# Main.net
KiCad netlist of a schematic drawn in Altium Designer
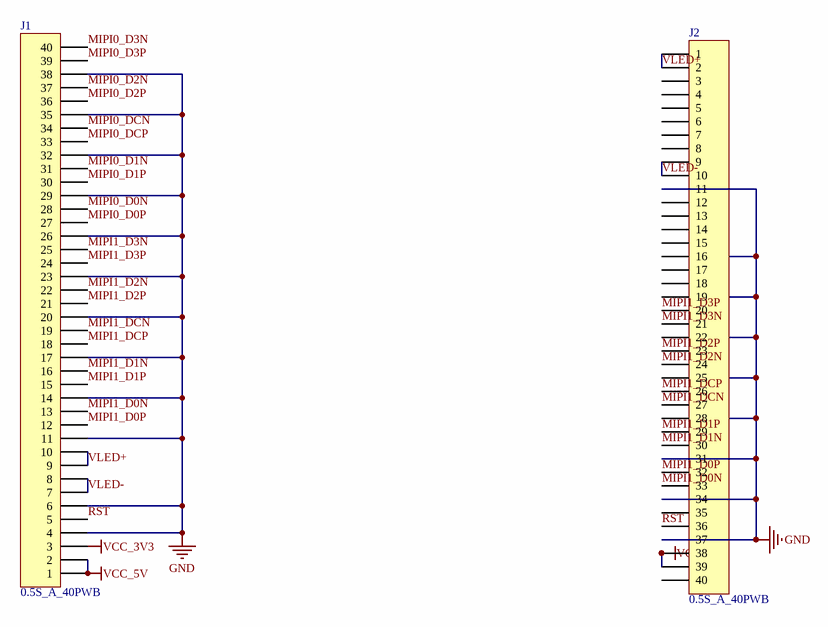
[diagram p0: Main.SchDoc]

(export (version "E")
  (design (tool "Eeschema 10.0.6"))
  (components
    (comp (ref "J1")
      (value "0.5S_A_40PWB")
      (footprint "FFC_0.5_40")
      (description "Header, 40-Pin")
      (fields (field (name "PUBLISHER") "Altium Limited"))
      (libsource (lib "MyPcbLib") (part "FPC40-0.5mm"))
    )
    (comp (ref "J2")
      (value "0.5S_A_40PWB")
      (footprint "FFC_0.5_40")
      (description "Header, 40-Pin")
      (fields (field (name "PUBLISHER") "Altium Limited"))
      (libsource (lib "") (part "FPC40-0.5mm_1"))
    )
  )
  (nets
    (net (code "1") (name "/MIPI0_D0N") (class "Default")
      (node (ref "J1") (pin "28") (pinfunction "28_28") (pintype "passive"))
    )
    (net (code "2") (name "/MIPI0_D0P") (class "Default")
      (node (ref "J1") (pin "27") (pinfunction "27_27") (pintype "passive"))
    )
    (net (code "3") (name "/MIPI0_D1N") (class "Default")
      (node (ref "J1") (pin "31") (pinfunction "31_31") (pintype "passive"))
    )
    (net (code "4") (name "/MIPI0_D1P") (class "Default")
      (node (ref "J1") (pin "30") (pinfunction "30_30") (pintype "passive"))
    )
    (net (code "5") (name "/MIPI0_D2N") (class "Default")
      (node (ref "J1") (pin "37") (pinfunction "37_37") (pintype "passive"))
    )
    (net (code "6") (name "/MIPI0_D2P") (class "Default")
      (node (ref "J1") (pin "36") (pinfunction "36_36") (pintype "passive"))
    )
    (net (code "7") (name "/MIPI0_D3N") (class "Default")
      (node (ref "J1") (pin "40") (pinfunction "40_40") (pintype "passive"))
    )
    (net (code "8") (name "/MIPI0_D3P") (class "Default")
      (node (ref "J1") (pin "39") (pinfunction "39_39") (pintype "passive"))
    )
    (net (code "9") (name "/MIPI0_DCN") (class "Default")
      (node (ref "J1") (pin "34") (pinfunction "34_34") (pintype "passive"))
    )
    (net (code "10") (name "/MIPI0_DCP") (class "Default")
      (node (ref "J1") (pin "33") (pinfunction "33_33") (pintype "passive"))
    )
    (net (code "11") (name "/MIPI1_D0N") (class "Default")
      (node (ref "J1") (pin "13") (pinfunction "13_13") (pintype "passive"))
      (node (ref "J2") (pin "33") (pinfunction "33_33") (pintype "passive"))
    )
    (net (code "12") (name "/MIPI1_D0P") (class "Default")
      (node (ref "J1") (pin "12") (pinfunction "12_12") (pintype "passive"))
      (node (ref "J2") (pin "32") (pinfunction "32_32") (pintype "passive"))
    )
    (net (code "13") (name "/MIPI1_D1N") (class "Default")
      (node (ref "J1") (pin "16") (pinfunction "16_16") (pintype "passive"))
      (node (ref "J2") (pin "30") (pinfunction "30_30") (pintype "passive"))
    )
    (net (code "14") (name "/MIPI1_D1P") (class "Default")
      (node (ref "J1") (pin "15") (pinfunction "15_15") (pintype "passive"))
      (node (ref "J2") (pin "29") (pinfunction "29_29") (pintype "passive"))
    )
    (net (code "15") (name "/MIPI1_D2N") (class "Default")
      (node (ref "J1") (pin "22") (pinfunction "22_22") (pintype "passive"))
      (node (ref "J2") (pin "24") (pinfunction "24_24") (pintype "passive"))
    )
    (net (code "16") (name "/MIPI1_D2P") (class "Default")
      (node (ref "J1") (pin "21") (pinfunction "21_21") (pintype "passive"))
      (node (ref "J2") (pin "23") (pinfunction "23_23") (pintype "passive"))
    )
    (net (code "17") (name "/MIPI1_D3N") (class "Default")
      (node (ref "J1") (pin "25") (pinfunction "25_25") (pintype "passive"))
      (node (ref "J2") (pin "21") (pinfunction "21_21") (pintype "passive"))
    )
    (net (code "18") (name "/MIPI1_D3P") (class "Default")
      (node (ref "J1") (pin "24") (pinfunction "24_24") (pintype "passive"))
      (node (ref "J2") (pin "20") (pinfunction "20_20") (pintype "passive"))
    )
    (net (code "19") (name "/MIPI1_DCN") (class "Default")
      (node (ref "J1") (pin "19") (pinfunction "19_19") (pintype "passive"))
      (node (ref "J2") (pin "27") (pinfunction "27_27") (pintype "passive"))
    )
    (net (code "20") (name "/MIPI1_DCP") (class "Default")
      (node (ref "J1") (pin "18") (pinfunction "18_18") (pintype "passive"))
      (node (ref "J2") (pin "26") (pinfunction "26_26") (pintype "passive"))
    )
    (net (code "21") (name "/RST") (class "Default")
      (node (ref "J1") (pin "5") (pinfunction "5_5") (pintype "passive"))
      (node (ref "J2") (pin "36") (pinfunction "36_36") (pintype "passive"))
    )
    (net (code "22") (name "/VLED+") (class "Default")
      (node (ref "J1") (pin "10") (pinfunction "10_10") (pintype "passive"))
      (node (ref "J1") (pin "9") (pinfunction "9_9") (pintype "passive"))
      (node (ref "J2") (pin "1") (pinfunction "1_1") (pintype "passive"))
      (node (ref "J2") (pin "2") (pinfunction "2_2") (pintype "passive"))
    )
    (net (code "23") (name "/VLED-") (class "Default")
      (node (ref "J1") (pin "7") (pinfunction "7_7") (pintype "passive"))
      (node (ref "J1") (pin "8") (pinfunction "8_8") (pintype "passive"))
      (node (ref "J2") (pin "10") (pinfunction "10_10") (pintype "passive"))
      (node (ref "J2") (pin "9") (pinfunction "9_9") (pintype "passive"))
    )
    (net (code "24") (name "GND") (class "Default")
      (node (ref "J1") (pin "11") (pinfunction "11_11") (pintype "passive"))
      (node (ref "J1") (pin "14") (pinfunction "14_14") (pintype "passive"))
      (node (ref "J1") (pin "17") (pinfunction "17_17") (pintype "passive"))
      (node (ref "J1") (pin "20") (pinfunction "20_20") (pintype "passive"))
      (node (ref "J1") (pin "23") (pinfunction "23_23") (pintype "passive"))
      (node (ref "J1") (pin "26") (pinfunction "26_26") (pintype "passive"))
      (node (ref "J1") (pin "29") (pinfunction "29_29") (pintype "passive"))
      (node (ref "J1") (pin "32") (pinfunction "32_32") (pintype "passive"))
      (node (ref "J1") (pin "35") (pinfunction "35_35") (pintype "passive"))
      (node (ref "J1") (pin "38") (pinfunction "38_38") (pintype "passive"))
      (node (ref "J1") (pin "4") (pinfunction "4_4") (pintype "passive"))
      (node (ref "J1") (pin "6") (pinfunction "6_6") (pintype "passive"))
      (node (ref "J2") (pin "11") (pinfunction "11_11") (pintype "passive"))
      (node (ref "J2") (pin "16") (pinfunction "16_16") (pintype "passive"))
      (node (ref "J2") (pin "19") (pinfunction "19_19") (pintype "passive"))
      (node (ref "J2") (pin "22") (pinfunction "22_22") (pintype "passive"))
      (node (ref "J2") (pin "25") (pinfunction "25_25") (pintype "passive"))
      (node (ref "J2") (pin "28") (pinfunction "28_28") (pintype "passive"))
      (node (ref "J2") (pin "31") (pinfunction "31_31") (pintype "passive"))
      (node (ref "J2") (pin "34") (pinfunction "34_34") (pintype "passive"))
      (node (ref "J2") (pin "37") (pinfunction "37_37") (pintype "passive"))
    )
    (net (code "25") (name "VCC_3V3") (class "Default")
      (node (ref "J1") (pin "3") (pinfunction "3_3") (pintype "passive"))
      (node (ref "J2") (pin "38") (pinfunction "38_38") (pintype "passive"))
      (node (ref "J2") (pin "39") (pinfunction "39_39") (pintype "passive"))
    )
    (net (code "26") (name "VCC_5V") (class "Default")
      (node (ref "J1") (pin "1") (pinfunction "1_1") (pintype "passive"))
      (node (ref "J1") (pin "2") (pinfunction "2_2") (pintype "passive"))
    )
    (net (code "27") (name "unconnected-(J2-Pad3)") (class "Default")
      (node (ref "J2") (pin "3") (pinfunction "3_3") (pintype "passive"))
    )
    (net (code "28") (name "unconnected-(J2-Pad4)") (class "Default")
      (node (ref "J2") (pin "4") (pinfunction "4_4") (pintype "passive"))
    )
    (net (code "29") (name "unconnected-(J2-Pad5)") (class "Default")
      (node (ref "J2") (pin "5") (pinfunction "5_5") (pintype "passive"))
    )
    (net (code "30") (name "unconnected-(J2-Pad6)") (class "Default")
      (node (ref "J2") (pin "6") (pinfunction "6_6") (pintype "passive"))
    )
    (net (code "31") (name "unconnected-(J2-Pad7)") (class "Default")
      (node (ref "J2") (pin "7") (pinfunction "7_7") (pintype "passive"))
    )
    (net (code "32") (name "unconnected-(J2-Pad8)") (class "Default")
      (node (ref "J2") (pin "8") (pinfunction "8_8") (pintype "passive"))
    )
    (net (code "33") (name "unconnected-(J2-Pad12)") (class "Default")
      (node (ref "J2") (pin "12") (pinfunction "12_12") (pintype "passive"))
    )
    (net (code "34") (name "unconnected-(J2-Pad13)") (class "Default")
      (node (ref "J2") (pin "13") (pinfunction "13_13") (pintype "passive"))
    )
    (net (code "35") (name "unconnected-(J2-Pad14)") (class "Default")
      (node (ref "J2") (pin "14") (pinfunction "14_14") (pintype "passive"))
    )
    (net (code "36") (name "unconnected-(J2-Pad15)") (class "Default")
      (node (ref "J2") (pin "15") (pinfunction "15_15") (pintype "passive"))
    )
    (net (code "37") (name "unconnected-(J2-Pad17)") (class "Default")
      (node (ref "J2") (pin "17") (pinfunction "17_17") (pintype "passive"))
    )
    (net (code "38") (name "unconnected-(J2-Pad18)") (class "Default")
      (node (ref "J2") (pin "18") (pinfunction "18_18") (pintype "passive"))
    )
    (net (code "39") (name "unconnected-(J2-Pad35)") (class "Default")
      (node (ref "J2") (pin "35") (pinfunction "35_35") (pintype "passive"))
    )
    (net (code "40") (name "unconnected-(J2-Pad40)") (class "Default")
      (node (ref "J2") (pin "40") (pinfunction "40_40") (pintype "passive"))
    )
  )
)
